# Scooter_-_Secondary_Board_-_Schematic.net
KiCad netlist of a schematic drawn in Altium Designer
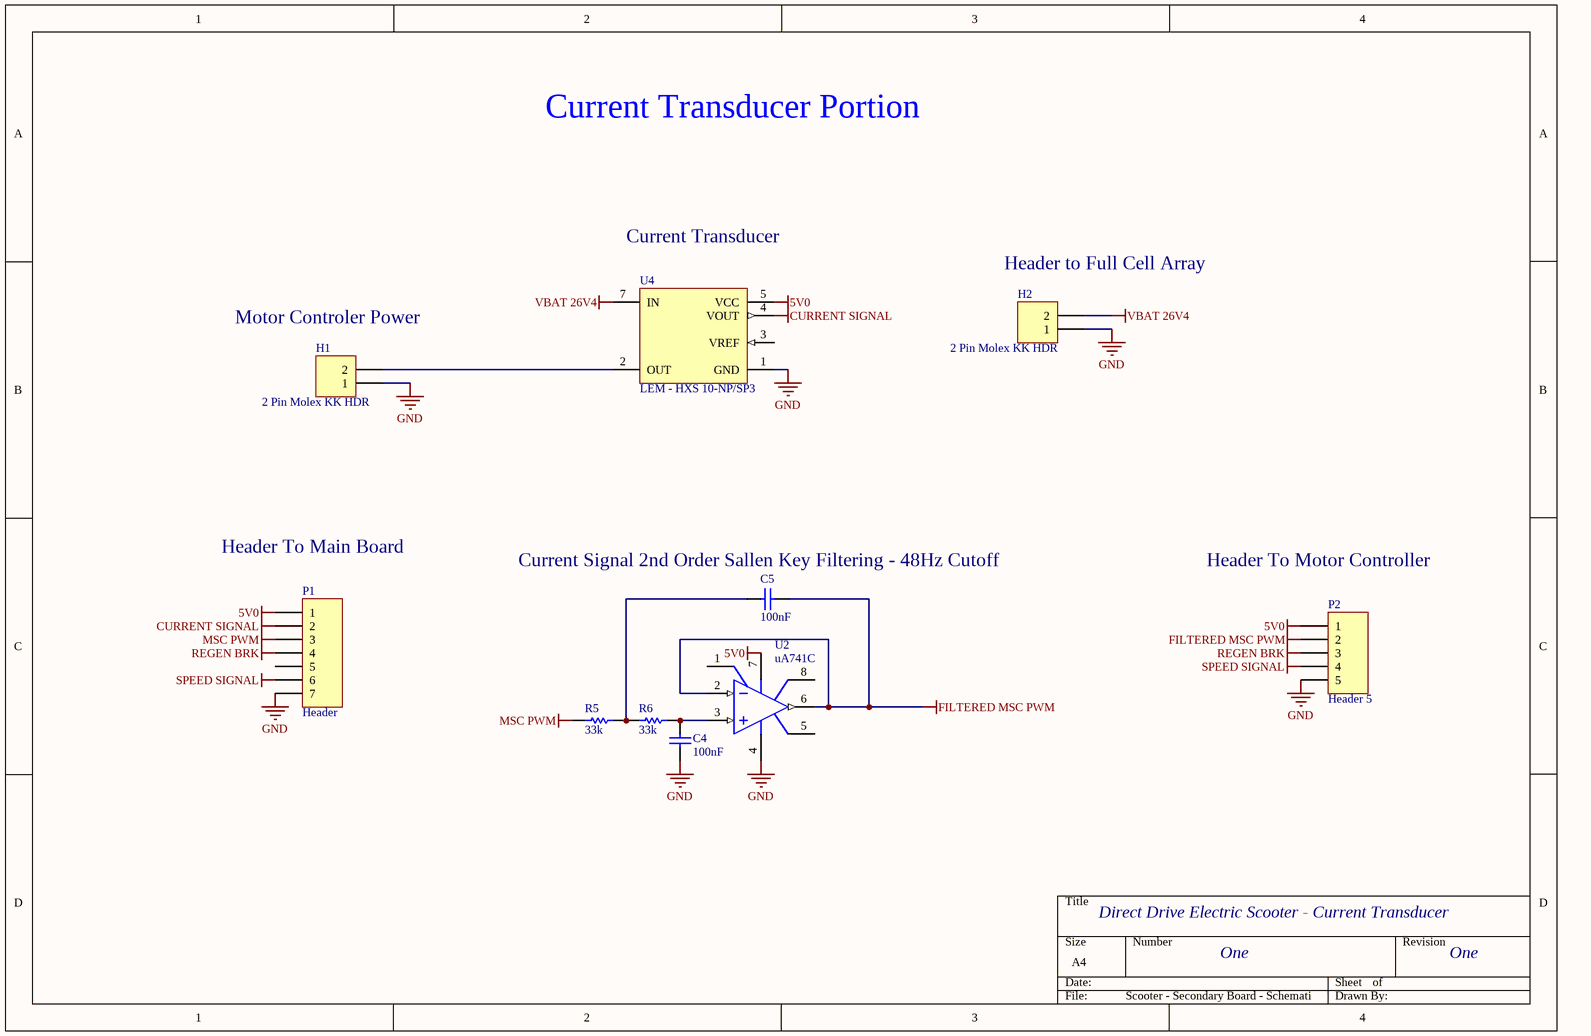
[diagram p0: Scooter - Secondary Board - Schematic.SchDoc]

(export (version "E")
  (design (tool "Eeschema 10.0.6"))
  (components
    (comp (ref "C4")
      (value "100nF")
      (footprint "CAPC1608L")
      (description "CAP CER 100nF X7R +-10% 50V 0603")
      (libsource (lib "ECE Components-Ver2") (part "CC_100nF_0603"))
    )
    (comp (ref "C5")
      (value "100nF")
      (footprint "CAPC1608L")
      (description "CAP CER 100nF X7R +-10% 50V 0603")
      (libsource (lib "ECE Components-Ver2") (part "CC_100nF_0603"))
    )
    (comp (ref "H1")
      (value "2 Pin Molex KK HDR")
      (footprint "MOLEX_KK_2_HDR")
      (description "CONN HEADER 2POS 2.54mm VERT_Thru Hole")
      (libsource (lib "CONNECTORS") (part "JA_MOLEX_KK_2POS"))
    )
    (comp (ref "H2")
      (value "2 Pin Molex KK HDR")
      (footprint "MOLEX_KK_2_HDR")
      (description "CONN HEADER 2POS 2.54mm VERT_Thru Hole")
      (libsource (lib "CONNECTORS") (part "JA_MOLEX_KK_2POS"))
    )
    (comp (ref "P1")
      (value "Header")
      (footprint "HDR1X7")
      (description "Header, 7-Pin")
      (fields (field (name "PUBLISHER") "Altium Limited"))
      (libsource (lib "Miscellaneous Connectors") (part "Header 7"))
    )
    (comp (ref "P2")
      (value "Header 5")
      (footprint "HDR1X5")
      (description "Header, 5-Pin")
      (fields (field (name "PUBLISHER") "Altium Limited"))
      (libsource (lib "Miscellaneous Connectors") (part "Header 5"))
    )
    (comp (ref "R5")
      (value "33k")
      (footprint "RESC1608L")
      (description "RES 10.0K OHM 1/10W 5% 0603 SMD")
      (libsource (lib "ECE Components-Ver2") (part "RS_10K"))
    )
    (comp (ref "R6")
      (value "33k")
      (footprint "RESC1608L")
      (description "RES 10.0K OHM 1/10W 5% 0603 SMD")
      (libsource (lib "ECE Components-Ver2") (part "RS_10K"))
    )
    (comp (ref "U2")
      (value "uA741C")
      (footprint "SO8_N")
      (description "High Performance Operational Amplifier")
      (fields (field (name "PUBLISHER") "Altium Limited"))
      (libsource (lib "TI Operational Amplifier") (part "LM101AJG"))
    )
    (comp (ref "U4")
      (value "LEM - HXS 10-NP/SP3")
      (footprint "PCBComponent_1")
      (fields (field (name "PUBLISHER") "Altium Limited"))
      (libsource (lib "Microchip Power Mgt Line Regulator") (part "TC1072-3.0VCH713"))
    )
  )
  (nets
    (net (code "1") (name "5V0") (class "Default")
      (node (ref "P1") (pin "1") (pinfunction "1_1") (pintype "passive"))
      (node (ref "P2") (pin "1") (pinfunction "1_1") (pintype "passive"))
      (node (ref "U2") (pin "7") (pinfunction "V+_7") (pintype "power_in"))
      (node (ref "U4") (pin "5") (pinfunction "VCC_5") (pintype "passive"))
    )
    (net (code "2") (name "CURRENT SIGNAL") (class "Default")
      (node (ref "P1") (pin "2") (pinfunction "2_2") (pintype "passive"))
      (node (ref "U4") (pin "4") (pinfunction "VOUT_4") (pintype "output"))
    )
    (net (code "3") (name "FILTERED MSC PWM") (class "Default")
      (node (ref "C5") (pin "1") (pinfunction "1_1") (pintype "passive"))
      (node (ref "P2") (pin "2") (pinfunction "2_2") (pintype "passive"))
      (node (ref "U2") (pin "2") (pinfunction "IN-_2") (pintype "input"))
      (node (ref "U2") (pin "6") (pinfunction "OUT_6") (pintype "output"))
    )
    (net (code "4") (name "GND") (class "Default")
      (node (ref "C4") (pin "1") (pinfunction "1_1") (pintype "passive"))
      (node (ref "H1") (pin "1") (pinfunction "1_1") (pintype "passive"))
      (node (ref "H2") (pin "1") (pinfunction "1_1") (pintype "passive"))
      (node (ref "P1") (pin "7") (pinfunction "7_7") (pintype "passive"))
      (node (ref "P2") (pin "5") (pinfunction "5_5") (pintype "passive"))
      (node (ref "U2") (pin "4") (pinfunction "V-_4") (pintype "power_in"))
      (node (ref "U4") (pin "1") (pinfunction "GND_1") (pintype "power_in"))
    )
    (net (code "5") (name "MSC PWM") (class "Default")
      (node (ref "P1") (pin "3") (pinfunction "3_3") (pintype "passive"))
      (node (ref "R5") (pin "2") (pinfunction "2_2") (pintype "passive"))
    )
    (net (code "6") (name "Net-(C5-Pad2)") (class "Default")
      (node (ref "C5") (pin "2") (pinfunction "2_2") (pintype "passive"))
      (node (ref "R5") (pin "1") (pinfunction "1_1") (pintype "passive"))
      (node (ref "R6") (pin "2") (pinfunction "2_2") (pintype "passive"))
    )
    (net (code "7") (name "Net-(U2-IN+)") (class "Default")
      (node (ref "C4") (pin "2") (pinfunction "2_2") (pintype "passive"))
      (node (ref "R6") (pin "1") (pinfunction "1_1") (pintype "passive"))
      (node (ref "U2") (pin "3") (pinfunction "IN+_3") (pintype "input"))
    )
    (net (code "8") (name "Net-(U4-OUT)") (class "Default")
      (node (ref "H1") (pin "2") (pinfunction "2_2") (pintype "passive"))
      (node (ref "U4") (pin "2") (pinfunction "OUT_2") (pintype "power_in"))
    )
    (net (code "9") (name "REGEN BRK") (class "Default")
      (node (ref "P1") (pin "4") (pinfunction "4_4") (pintype "passive"))
      (node (ref "P2") (pin "3") (pinfunction "3_3") (pintype "passive"))
    )
    (net (code "10") (name "SPEED SIGNAL") (class "Default")
      (node (ref "P1") (pin "6") (pinfunction "6_6") (pintype "passive"))
      (node (ref "P2") (pin "4") (pinfunction "4_4") (pintype "passive"))
    )
    (net (code "11") (name "VBAT 26V4") (class "Default")
      (node (ref "H2") (pin "2") (pinfunction "2_2") (pintype "passive"))
      (node (ref "U4") (pin "7") (pinfunction "IN_7") (pintype "power_in"))
    )
    (net (code "12") (name "unconnected-(P1-Pad5)") (class "Default")
      (node (ref "P1") (pin "5") (pinfunction "5_5") (pintype "passive"))
    )
    (net (code "13") (name "unconnected-(U2-BAL1{slash}CMPEN-Pad1)") (class "Default")
      (node (ref "U2") (pin "1") (pinfunction "BAL1/CMPEN_1") (pintype "passive"))
    )
    (net (code "14") (name "unconnected-(U2-BAL2-Pad5)") (class "Default")
      (node (ref "U2") (pin "5") (pinfunction "BAL2_5") (pintype "passive"))
    )
    (net (code "15") (name "unconnected-(U2-CMPEN-Pad8)") (class "Default")
      (node (ref "U2") (pin "8") (pinfunction "CMPEN_8") (pintype "passive"))
    )
    (net (code "16") (name "unconnected-(U4-VREF-Pad3)") (class "Default")
      (node (ref "U4") (pin "3") (pinfunction "VREF_3") (pintype "input"))
    )
  )
)
